# INA226_Current_Monitor.net
KiCad netlist of a schematic drawn in Altium Designer
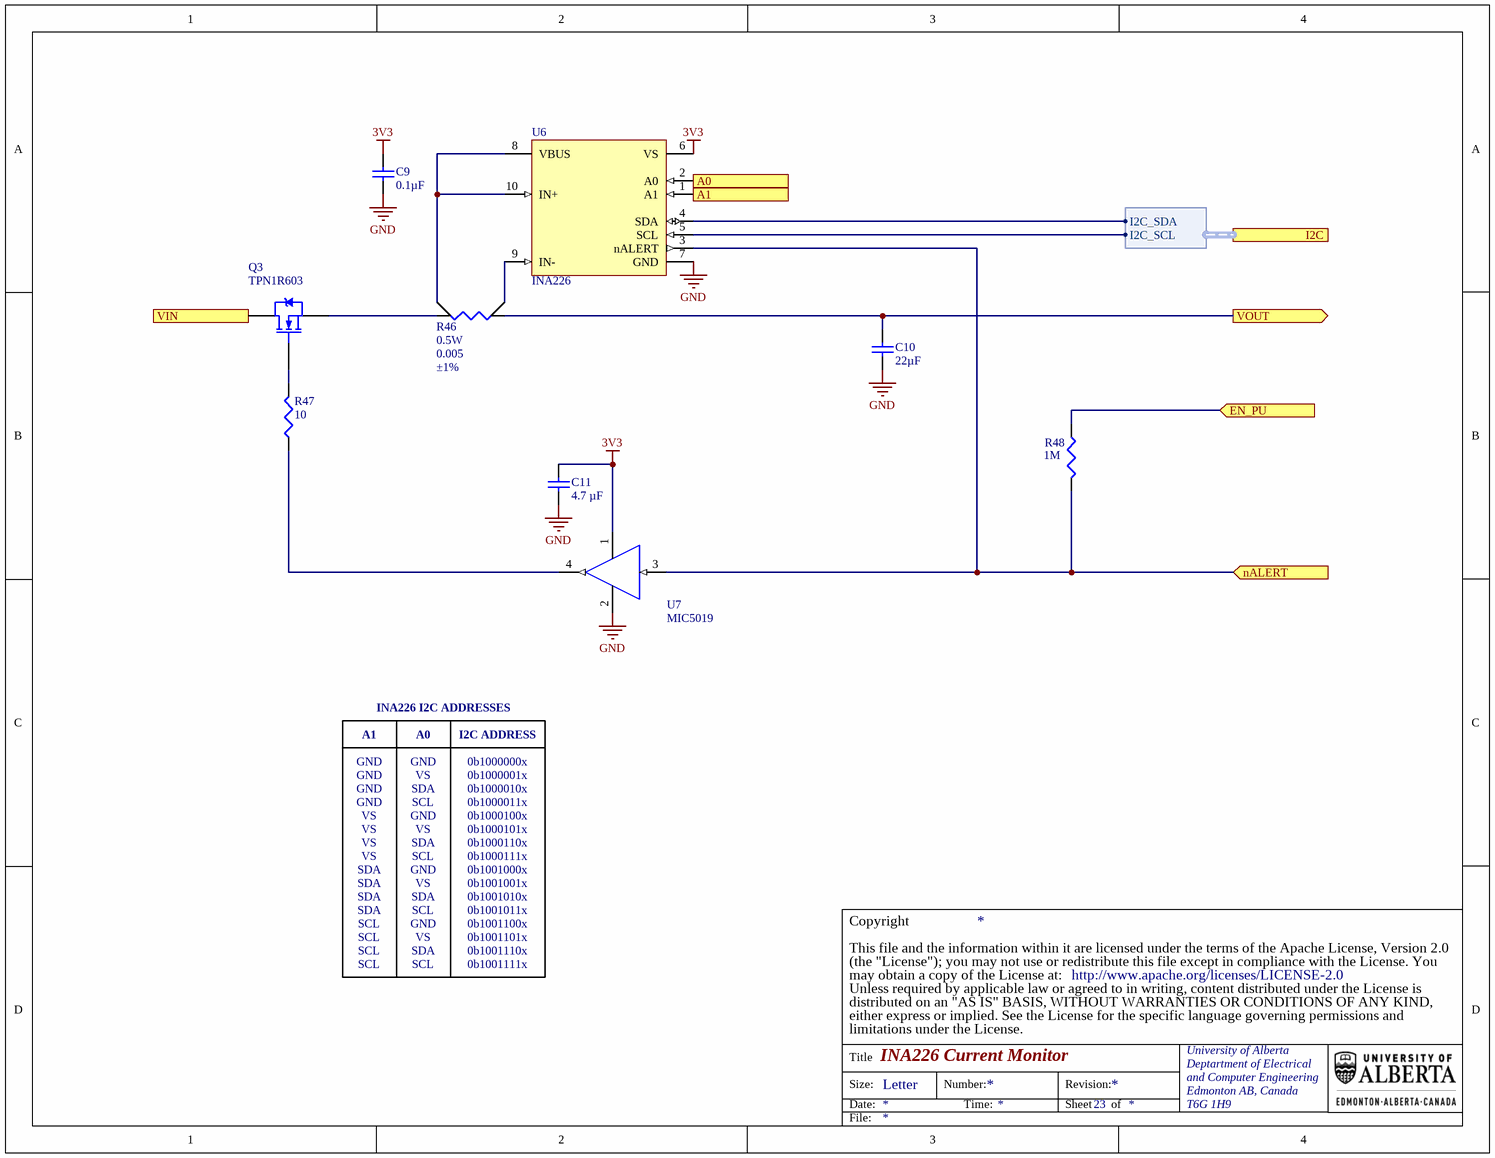
[diagram p0: INA226 Current Monitor.SchDoc]

(export (version "E")
  (design (tool "Eeschema 10.0.6"))
  (components
    (comp (ref "C9")
      (value "0.1µF")
      (footprint "TDK-CGA2B")
      (description "CAP CER 0.1UF 50V X7R 0402")
      (fields
        (field (name "PART NUMBER") "PC-TDK-02259")
        (field (name "MANUFACTURER PART NUMBER") "CGA2B3X7R1H104K050BB")
        (field (name "PUBLISHER") "AlbertaSat")
      )
      (libsource (lib "Database") (part "Cap"))
    )
    (comp (ref "C10")
      (value "22µF")
      (footprint "TY-1206L")
      (description "CAP CER 22UF 16V X7R 1206")
      (fields
        (field (name "PART NUMBER") "PC-TY-00721")
        (field (name "MANUFACTURER PART NUMBER") "EMK316BB7226ML-T")
        (field (name "PUBLISHER") "AlbertaSat")
      )
      (libsource (lib "Database") (part "Cap"))
    )
    (comp (ref "C11")
      (value "4.7 µF")
      (footprint "MUR-GRM188")
      (description "CAP CER 4.7UF 16V X7R 0603")
      (fields
        (field (name "PART NUMBER") "10165")
        (field (name "MANUFACTURER PART NUMBER") "GRM188Z71C475KE21D")
        (field (name "PUBLISHER") "Altium Limited")
      )
      (libsource (lib "Database") (part "Cap"))
    )
    (comp (ref "Q3")
      (value "TPN1R603")
      (footprint "TOSH-S-3X1S")
      (description "X35 PB-F POWER MOSFET TRANSISTOR")
      (fields
        (field (name "PART NUMBER") "PU-TOSH-00002")
        (field (name "MANUFACTURER PART NUMBER") "TPN1R603PL,L1Q")
        (field (name "PUBLISHER") "AlbertaSat")
      )
      (libsource (lib "Database") (part "TPN1R603PL,L1Q"))
    )
    (comp (ref "R46")
      (value "0.005")
      (footprint "BRN-CRF0805")
      (description "RES 0.005 OHM 1% 1/2W 0805")
      (fields
        (field (name "POWER - RATED") "0.5W")
        (field (name "TOLERANCE") "±1%")
        (field (name "PART NUMBER") "PR-BRN-00023")
        (field (name "MANUFACTURER PART NUMBER") "CRF0805-FZ-R005ELF")
        (field (name "PUBLISHER") "AlbertaSat")
      )
      (libsource (lib "Database") (part "Res Sense"))
    )
    (comp (ref "R47")
      (value "10")
      (footprint "PANA-ERA2A")
      (description "RES SMD 10 OHM 0.5% 1/16W 0402")
      (fields
        (field (name "PART NUMBER") "13235")
        (field (name "MANUFACTURER PART NUMBER") "ERA-2AKD100X")
        (field (name "PUBLISHER") "Altium Limited")
      )
      (libsource (lib "Database") (part "Res3"))
    )
    (comp (ref "R48")
      (value "1M")
      (footprint "PANA-ERJ2R")
      (description "RES SMD 1M OHM 1% 1/10W 0402")
      (fields
        (field (name "PART NUMBER") "19704")
        (field (name "MANUFACTURER PART NUMBER") "ERJ-2RKF1004X")
        (field (name "PUBLISHER") "Altium Limited")
      )
      (libsource (lib "Database") (part "Res3"))
    )
    (comp (ref "U6")
      (value "INA226")
      (footprint "TI-DGS")
      (description "IC MONITOR PWR/CURR BIDIR 10MSOP")
      (fields (field (name "PART NUMBER") "19") (field (name "MANUFACTURER PART NUMBER") "INA226AQDGSRQ1"))
      (libsource (lib "Database") (part "INA226AQ"))
    )
    (comp (ref "U7")
      (value "MIC5019")
      (footprint "MCP-MIC5019")
      (description "IC GATE DRVR HIGH-SIDE 4TQFN")
      (fields
        (field (name "PART NUMBER") "PU-MCP-00008")
        (field (name "MANUFACTURER PART NUMBER") "MIC5019YFT-TR")
        (field (name "PUBLISHER") "AlbertaSat")
      )
      (libsource (lib "Database") (part "MIC5019YFT-TR"))
    )
  )
  (nets
    (net (code "2") (name "/A0") (class "Default")
      (node (ref "U6") (pin "2") (pinfunction "A0_2") (pintype "input"))
    )
    (net (code "3") (name "/A1") (class "Default")
      (node (ref "U6") (pin "1") (pinfunction "A1_1") (pintype "input"))
    )
    (net (code "4") (name "/EN_PU") (class "Default")
      (node (ref "R48") (pin "2") (pinfunction "2_2") (pintype "passive"))
    )
    (net (code "5") (name "/I2C_SCL") (class "Default")
      (node (ref "U6") (pin "5") (pinfunction "SCL_5") (pintype "input"))
    )
    (net (code "6") (name "/I2C_SDA") (class "Default")
      (node (ref "U6") (pin "4") (pinfunction "SDA_4") (pintype "bidirectional"))
    )
    (net (code "7") (name "/VIN") (class "Default")
      (node (ref "Q3") (pin "2") (pinfunction "D_2") (pintype "passive"))
    )
    (net (code "8") (name "/VOUT") (class "Default")
      (node (ref "C10") (pin "2") (pinfunction "2_2") (pintype "passive"))
      (node (ref "R46") (pin "2") (pinfunction "I2_2") (pintype "passive"))
    )
    (net (code "9") (name "/nALERT") (class "Default")
      (node (ref "R48") (pin "1") (pinfunction "1_1") (pintype "passive"))
      (node (ref "U6") (pin "3") (pinfunction "nALERT_3") (pintype "output"))
      (node (ref "U7") (pin "3") (pinfunction "IN_3") (pintype "input"))
    )
    (net (code "11") (name "3V3") (class "Default")
      (node (ref "C11") (pin "2") (pinfunction "2_2") (pintype "passive"))
      (node (ref "C9") (pin "2") (pinfunction "2_2") (pintype "passive"))
      (node (ref "U6") (pin "6") (pinfunction "VS_6") (pintype "passive"))
      (node (ref "U7") (pin "1") (pinfunction "VDD_1") (pintype "power_in"))
    )
    (net (code "12") (name "GND") (class "Default")
      (node (ref "C10") (pin "1") (pinfunction "1_1") (pintype "passive"))
      (node (ref "C11") (pin "1") (pinfunction "1_1") (pintype "passive"))
      (node (ref "C9") (pin "1") (pinfunction "1_1") (pintype "passive"))
      (node (ref "U6") (pin "7") (pinfunction "GND_7") (pintype "power_in"))
      (node (ref "U7") (pin "2") (pinfunction "GND_2") (pintype "power_in"))
    )
    (net (code "13") (name "Net-(Q3-G)") (class "Default")
      (node (ref "Q3") (pin "1") (pinfunction "G_1") (pintype "passive"))
      (node (ref "R47") (pin "2") (pinfunction "2_2") (pintype "passive"))
    )
    (net (code "14") (name "Net-(Q3-S)") (class "Default")
      (node (ref "Q3") (pin "3") (pinfunction "S_3") (pintype "passive"))
      (node (ref "R46") (pin "1") (pinfunction "I1_1") (pintype "passive"))
    )
    (net (code "15") (name "Net-(R46-S1)") (class "Default")
      (node (ref "R46") (pin "4") (pinfunction "S1_4") (pintype "passive"))
      (node (ref "U6") (pin "10") (pinfunction "IN+_10") (pintype "input"))
      (node (ref "U6") (pin "8") (pinfunction "VBUS_8") (pintype "power_in"))
    )
    (net (code "16") (name "Net-(R46-S2)") (class "Default")
      (node (ref "R46") (pin "3") (pinfunction "S2_3") (pintype "passive"))
      (node (ref "U6") (pin "9") (pinfunction "IN-_9") (pintype "input"))
    )
    (net (code "17") (name "Net-(U7-OUT)") (class "Default")
      (node (ref "R47") (pin "1") (pinfunction "1_1") (pintype "passive"))
      (node (ref "U7") (pin "4") (pinfunction "OUT_4") (pintype "output"))
    )
  )
)
